# Geiger.net
KiCad netlist of a schematic drawn in Altium Designer
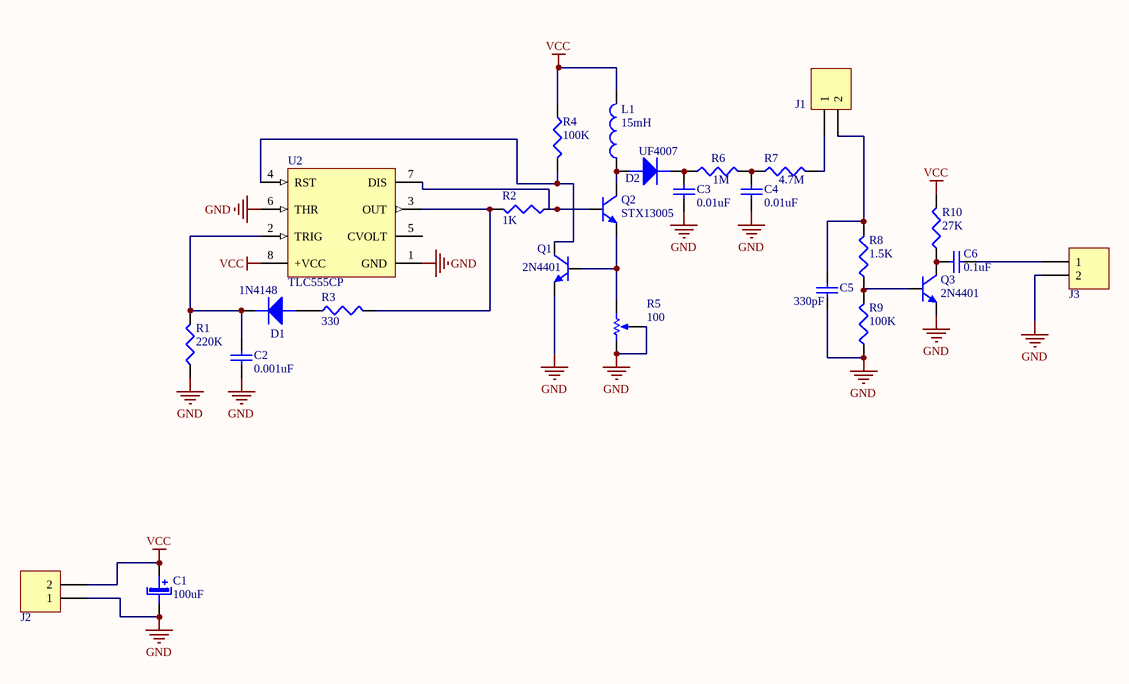
[diagram p0: Geiger.SchDoc]

(export (version "E")
  (design (tool "Eeschema 10.0.6"))
  (components
    (comp (ref "C1")
      (value "100uF")
      (footprint "CAPPR2-5x6.8")
      (description "Condensateur polarisé")
      (fields (field (name "Comment") "Cond pol axial") (field (name "DESIGNER") "ECAM 2004"))
      (libsource (lib "Geiger") (part "Cond pol axial"))
    )
    (comp (ref "C2")
      (value "0.001uF")
      (footprint "CAPR2.54-5.1x3.2")
      (description "Condensateur")
      (fields (field (name "DESIGNER") "ECAM 2004"))
      (libsource (lib "Geiger") (part "Condensateur"))
    )
    (comp (ref "C3")
      (value "0.01uF")
      (footprint "CAPPR5-5x5")
      (description "Condensateur")
      (fields (field (name "DESIGNER") "ECAM 2004"))
      (libsource (lib "Geiger") (part "Condensateur"))
    )
    (comp (ref "C4")
      (value "0.01uF")
      (footprint "CAPPR5-5x5")
      (description "Condensateur")
      (fields (field (name "DESIGNER") "ECAM 2004"))
      (libsource (lib "Geiger") (part "Condensateur"))
    )
    (comp (ref "C5")
      (value "330pF")
      (footprint "CAPR2.54-5.1x3.2")
      (description "Condensateur")
      (fields (field (name "DESIGNER") "ECAM 2004"))
      (libsource (lib "Geiger") (part "Condensateur"))
    )
    (comp (ref "C6")
      (value "0.1uF")
      (footprint "CAPR2.54-5.1x3.2")
      (description "Condensateur")
      (fields (field (name "DESIGNER") "ECAM 2004"))
      (libsource (lib "Geiger") (part "Condensateur"))
    )
    (comp (ref "D1")
      (value "1N4148")
      (footprint "AXIAL-0.3")
      (description "Diode")
      (fields (field (name "DESIGNER") "ECAM 2003"))
      (libsource (lib "Geiger") (part "Diode"))
    )
    (comp (ref "D2")
      (value "Diode")
      (footprint "DIODE-0.4")
      (fields (field (name "TYPE") "UF4007") (field (name "DESIGNER") "ECAM 2003"))
      (libsource (lib "Geiger") (part "Diode"))
    )
    (comp (ref "J1")
      (value "Connecteur 2")
      (footprint "HDR1X2")
      (description "Connecteur")
      (fields (field (name "DESIGNER") "ECAM 2005"))
      (libsource (lib "") (part "Connecteur 2_1"))
    )
    (comp (ref "J2")
      (value "Connecteur 2")
      (footprint "HDR1X2")
      (description "Connecteur")
      (fields (field (name "DESIGNER") "ECAM 2005"))
      (libsource (lib "") (part "Connecteur 2_2"))
    )
    (comp (ref "J3")
      (value "Connecteur 2")
      (footprint "HDR1X2")
      (description "Connecteur")
      (fields (field (name "DESIGNER") "ECAM 2005"))
      (libsource (lib "Geiger") (part "Connecteur 2"))
    )
    (comp (ref "L1")
      (value "15mH")
      (footprint "CAPPR7.5-16x35")
      (description "Inductance")
      (fields (field (name "DESIGNER") "ECAM 2003"))
      (libsource (lib "Geiger") (part "Inductance"))
    )
    (comp (ref "Q1")
      (value "2N4401")
      (footprint "TO-92")
      (description "Transistor Bipolaire")
      (fields (field (name "Comment") "NPN") (field (name "DESIGNER") "ECAM 2002"))
      (libsource (lib "Geiger") (part "NPN"))
    )
    (comp (ref "Q2")
      (value "STX13005")
      (footprint "TO-92 - Bis")
      (description "Transistor Bipolaire")
      (fields (field (name "Comment") "NPN") (field (name "DESIGNER") "ECAM 2002"))
      (libsource (lib "Geiger") (part "NPN"))
    )
    (comp (ref "Q3")
      (value "2N4401")
      (footprint "TO-92")
      (description "Transistor Bipolaire")
      (fields (field (name "Comment") "NPN") (field (name "DESIGNER") "ECAM 2002"))
      (libsource (lib "Geiger") (part "NPN"))
    )
    (comp (ref "R1")
      (value "220K")
      (footprint "AXIAL-0.4")
      (description "Résistance standard")
      (fields (field (name "Comment") "Résistance") (field (name "DESIGNER") "ECAM 2005"))
      (libsource (lib "Geiger") (part "Résistance"))
    )
    (comp (ref "R2")
      (value "1K")
      (footprint "AXIAL-0.4")
      (description "Résistance standard")
      (fields (field (name "Comment") "Résistance") (field (name "DESIGNER") "ECAM 2005"))
      (libsource (lib "Geiger") (part "Résistance"))
    )
    (comp (ref "R3")
      (value "330")
      (footprint "AXIAL-0.4")
      (description "Résistance standard")
      (fields (field (name "Comment") "Résistance") (field (name "DESIGNER") "ECAM 2005"))
      (libsource (lib "Geiger") (part "Résistance"))
    )
    (comp (ref "R4")
      (value "100K")
      (footprint "AXIAL-0.4")
      (description "Résistance standard")
      (fields (field (name "Comment") "Résistance") (field (name "DESIGNER") "ECAM 2005"))
      (libsource (lib "Geiger") (part "Résistance"))
    )
    (comp (ref "R5")
      (value "Potentiomètre")
      (footprint "VR5")
      (fields (field (name "SET POSITION") "100") (field (name "DESIGNER") "ECAM 2002"))
      (libsource (lib "Geiger") (part "Potentiomètre"))
    )
    (comp (ref "R6")
      (value "1M")
      (footprint "AXIAL-0.4")
      (description "Résistance standard")
      (fields (field (name "Comment") "Résistance") (field (name "DESIGNER") "ECAM 2005"))
      (libsource (lib "Geiger") (part "Résistance"))
    )
    (comp (ref "R7")
      (value "4.7M")
      (footprint "AXIAL-0.4")
      (description "Résistance standard")
      (fields (field (name "Comment") "Résistance") (field (name "DESIGNER") "ECAM 2005"))
      (libsource (lib "Geiger") (part "Résistance"))
    )
    (comp (ref "R8")
      (value "1.5K")
      (footprint "AXIAL-0.4")
      (description "Résistance standard")
      (fields (field (name "Comment") "Résistance") (field (name "DESIGNER") "ECAM 2005"))
      (libsource (lib "Geiger") (part "Résistance"))
    )
    (comp (ref "R9")
      (value "100K")
      (footprint "AXIAL-0.4")
      (description "Résistance standard")
      (fields (field (name "Comment") "Résistance") (field (name "DESIGNER") "ECAM 2005"))
      (libsource (lib "Geiger") (part "Résistance"))
    )
    (comp (ref "R10")
      (value "27K")
      (footprint "AXIAL-0.4")
      (description "Résistance standard")
      (fields (field (name "Comment") "Résistance") (field (name "DESIGNER") "ECAM 2005"))
      (libsource (lib "Geiger") (part "Résistance"))
    )
    (comp (ref "U2")
      (value "TLC555CP")
      (footprint "DIP8")
      (description "Timer, 8-pin MDIP")
      (fields
        (field (name "PARTNUMBER") "LM555CN")
        (field (name "MANUFACTURER") "National Semiconductor")
        (field (name "PUBLISHER") "Altium Limited")
      )
      (libsource (lib "Geiger") (part "LM555CN"))
    )
  )
  (nets
    (net (code "1") (name "GND") (class "Default")
      (node (ref "C1") (pin "2") (pinfunction "-_2") (pintype "passive"))
      (node (ref "C2") (pin "1") (pinfunction "1_1") (pintype "passive"))
      (node (ref "C3") (pin "2") (pinfunction "2_2") (pintype "passive"))
      (node (ref "C4") (pin "2") (pinfunction "2_2") (pintype "passive"))
      (node (ref "C5") (pin "2") (pinfunction "2_2") (pintype "passive"))
      (node (ref "J2") (pin "1") (pinfunction "1_1") (pintype "passive"))
      (node (ref "J3") (pin "2") (pinfunction "2_2") (pintype "passive"))
      (node (ref "Q1") (pin "1") (pinfunction "E_1") (pintype "passive"))
      (node (ref "Q3") (pin "1") (pinfunction "E_1") (pintype "passive"))
      (node (ref "R1") (pin "1") (pinfunction "1_1") (pintype "passive"))
      (node (ref "R5") (pin "1") (pinfunction "TOP_1") (pintype "passive"))
      (node (ref "R5") (pin "3") (pinfunction "TAP_3") (pintype "passive"))
      (node (ref "R9") (pin "1") (pinfunction "1_1") (pintype "passive"))
      (node (ref "U2") (pin "1") (pinfunction "GND_1") (pintype "power_in"))
      (node (ref "U2") (pin "6") (pinfunction "THR_6") (pintype "input"))
    )
    (net (code "2") (name "Net-(C4-Pad1)") (class "Default")
      (node (ref "C4") (pin "1") (pinfunction "1_1") (pintype "passive"))
      (node (ref "R6") (pin "2") (pinfunction "2_2") (pintype "passive"))
      (node (ref "R7") (pin "1") (pinfunction "1_1") (pintype "passive"))
    )
    (net (code "3") (name "Net-(C5-Pad1)") (class "Default")
      (node (ref "C5") (pin "1") (pinfunction "1_1") (pintype "passive"))
      (node (ref "J1") (pin "2") (pinfunction "2_2") (pintype "passive"))
      (node (ref "R8") (pin "2") (pinfunction "2_2") (pintype "passive"))
    )
    (net (code "4") (name "Net-(C6-Pad2)") (class "Default")
      (node (ref "C6") (pin "2") (pinfunction "2_2") (pintype "passive"))
      (node (ref "J3") (pin "1") (pinfunction "1_1") (pintype "passive"))
    )
    (net (code "5") (name "Net-(D1-A)") (class "Default")
      (node (ref "D1") (pin "1") (pinfunction "A_1") (pintype "passive"))
      (node (ref "R3") (pin "1") (pinfunction "1_1") (pintype "passive"))
    )
    (net (code "6") (name "Net-(D1-K)") (class "Default")
      (node (ref "C2") (pin "2") (pinfunction "2_2") (pintype "passive"))
      (node (ref "D1") (pin "2") (pinfunction "K_2") (pintype "passive"))
      (node (ref "R1") (pin "2") (pinfunction "2_2") (pintype "passive"))
      (node (ref "U2") (pin "2") (pinfunction "TRIG_2") (pintype "input"))
    )
    (net (code "7") (name "Net-(D2-A)") (class "Default")
      (node (ref "D2") (pin "1") (pinfunction "A_1") (pintype "passive"))
      (node (ref "L1") (pin "1") (pinfunction "1_1") (pintype "passive"))
      (node (ref "Q2") (pin "3") (pinfunction "C_3") (pintype "passive"))
    )
    (net (code "8") (name "Net-(D2-K)") (class "Default")
      (node (ref "C3") (pin "1") (pinfunction "1_1") (pintype "passive"))
      (node (ref "D2") (pin "2") (pinfunction "K_2") (pintype "passive"))
      (node (ref "R6") (pin "1") (pinfunction "1_1") (pintype "passive"))
    )
    (net (code "9") (name "Net-(J1-Pad1)") (class "Default")
      (node (ref "J1") (pin "1") (pinfunction "1_1") (pintype "passive"))
      (node (ref "R7") (pin "2") (pinfunction "2_2") (pintype "passive"))
    )
    (net (code "10") (name "Net-(Q1-B)") (class "Default")
      (node (ref "Q1") (pin "2") (pinfunction "B_2") (pintype "passive"))
      (node (ref "Q2") (pin "1") (pinfunction "E_1") (pintype "passive"))
      (node (ref "R5") (pin "2") (pinfunction "BOT_2") (pintype "passive"))
    )
    (net (code "11") (name "Net-(Q1-C)") (class "Default")
      (node (ref "Q1") (pin "3") (pinfunction "C_3") (pintype "passive"))
      (node (ref "R4") (pin "2") (pinfunction "2_2") (pintype "passive"))
      (node (ref "U2") (pin "4") (pinfunction "RST_4") (pintype "input"))
    )
    (net (code "12") (name "Net-(Q2-B)") (class "Default")
      (node (ref "Q2") (pin "2") (pinfunction "B_2") (pintype "passive"))
      (node (ref "R2") (pin "1") (pinfunction "1_1") (pintype "passive"))
      (node (ref "U2") (pin "7") (pinfunction "DIS_7") (pintype "open_collector"))
    )
    (net (code "13") (name "Net-(Q3-B)") (class "Default")
      (node (ref "Q3") (pin "2") (pinfunction "B_2") (pintype "passive"))
      (node (ref "R8") (pin "1") (pinfunction "1_1") (pintype "passive"))
      (node (ref "R9") (pin "2") (pinfunction "2_2") (pintype "passive"))
    )
    (net (code "14") (name "Net-(Q3-C)") (class "Default")
      (node (ref "C6") (pin "1") (pinfunction "1_1") (pintype "passive"))
      (node (ref "Q3") (pin "3") (pinfunction "C_3") (pintype "passive"))
      (node (ref "R10") (pin "1") (pinfunction "1_1") (pintype "passive"))
    )
    (net (code "15") (name "Net-(U2-OUT)") (class "Default")
      (node (ref "R2") (pin "2") (pinfunction "2_2") (pintype "passive"))
      (node (ref "R3") (pin "2") (pinfunction "2_2") (pintype "passive"))
      (node (ref "U2") (pin "3") (pinfunction "OUT_3") (pintype "output"))
    )
    (net (code "16") (name "VCC") (class "Default")
      (node (ref "C1") (pin "1") (pinfunction "+_1") (pintype "passive"))
      (node (ref "J2") (pin "2") (pinfunction "2_2") (pintype "passive"))
      (node (ref "L1") (pin "2") (pinfunction "2_2") (pintype "passive"))
      (node (ref "R10") (pin "2") (pinfunction "2_2") (pintype "passive"))
      (node (ref "R4") (pin "1") (pinfunction "1_1") (pintype "passive"))
      (node (ref "U2") (pin "8") (pinfunction "+VCC_8") (pintype "power_in"))
    )
    (net (code "17") (name "unconnected-(U2-CVOLT-Pad5)") (class "Default")
      (node (ref "U2") (pin "5") (pinfunction "CVOLT_5") (pintype "passive"))
    )
  )
)
